# ESP8266_daughter_board.net
KiCad netlist of a schematic drawn in EAGLE
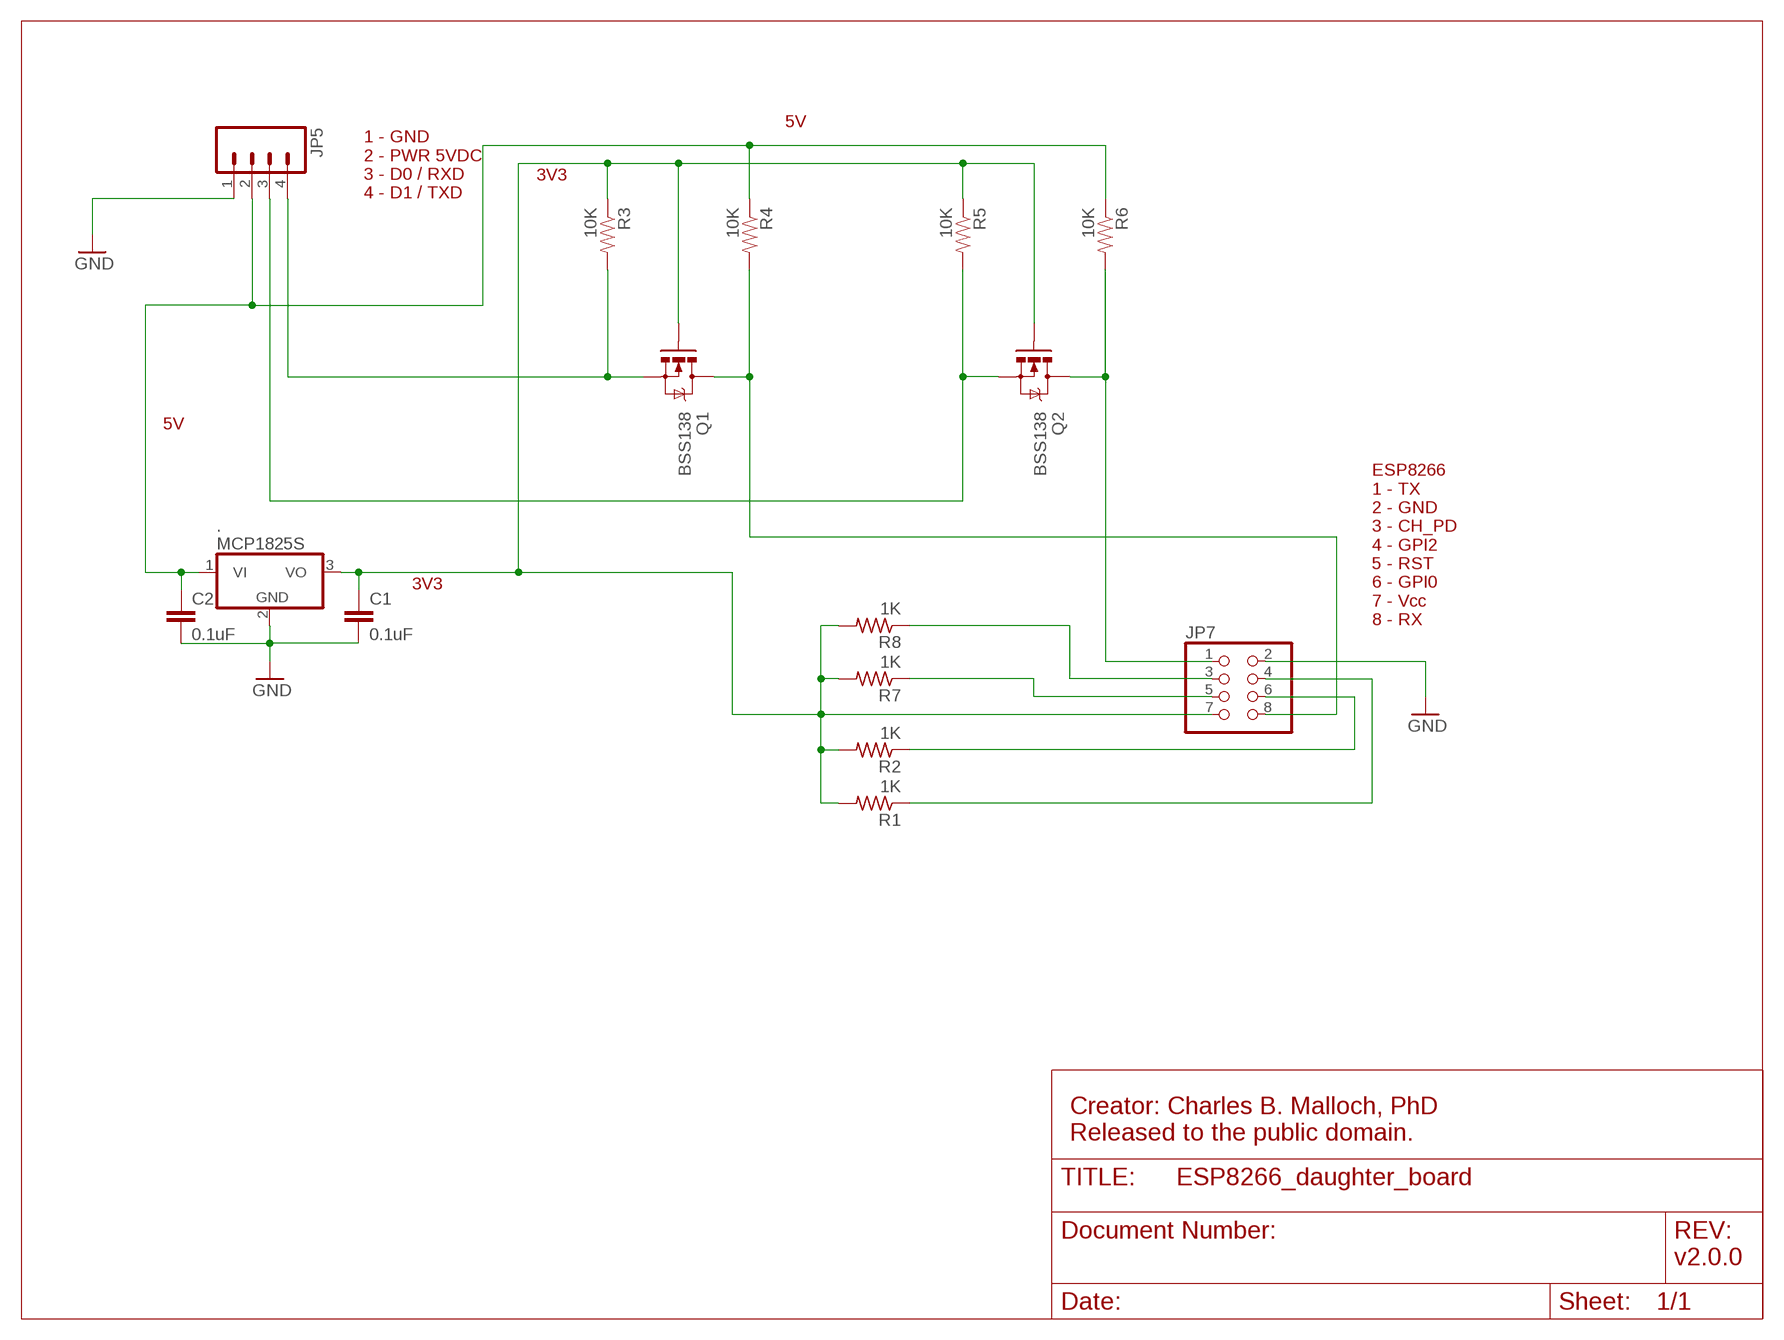
[diagram p0: schematic, sheet 1]

(export (version "E")
  (design (tool "Eeschema 10.0.6"))
  (components
    (comp (ref ".")
      (value "MCP1825S")
      (footprint "eagle-import:SOT223")
      (libsource (lib "eagle-import") (part "MCP1703DB"))
    )
    (comp (ref "C1")
      (value "0.1uF")
      (footprint "eagle-import:CAP-PTH-SMALLEZ")
      (libsource (lib "eagle-import") (part "CAPEZ"))
    )
    (comp (ref "C2")
      (value "0.1uF")
      (footprint "eagle-import:CAP-PTH-SMALLEZ")
      (libsource (lib "eagle-import") (part "CAPEZ"))
    )
    (comp (ref "JP5")
      (value "M04LOCK_LONGPADS")
      (footprint "eagle-import:1X04_LOCK_LONGPADS")
      (libsource (lib "eagle-import") (part "M04LOCK_LONGPADS"))
    )
    (comp (ref "JP7")
      (value "PINHD-2X4")
      (footprint "eagle-import:2X04")
      (libsource (lib "eagle-import") (part "PINHD-2X4"))
    )
    (comp (ref "Q1")
      (value "BSS138")
      (footprint "eagle-import:SOT23-3")
      (libsource (lib "eagle-import") (part "BSS138TRANS-00830"))
    )
    (comp (ref "Q2")
      (value "BSS138")
      (footprint "eagle-import:SOT23-3")
      (libsource (lib "eagle-import") (part "BSS138TRANS-00830"))
    )
    (comp (ref "R1")
      (value "1K")
      (footprint "eagle-import:0204_7")
      (libsource (lib "eagle-import") (part "R-US_0204/7"))
    )
    (comp (ref "R2")
      (value "1K")
      (footprint "eagle-import:0204_7")
      (libsource (lib "eagle-import") (part "R-US_0204/7"))
    )
    (comp (ref "R3")
      (value "10K")
      (footprint "eagle-import:1206")
      (libsource (lib "eagle-import") (part "RESISTOR1206"))
    )
    (comp (ref "R4")
      (value "10K")
      (footprint "eagle-import:1206")
      (libsource (lib "eagle-import") (part "RESISTOR1206"))
    )
    (comp (ref "R5")
      (value "10K")
      (footprint "eagle-import:1206")
      (libsource (lib "eagle-import") (part "RESISTOR1206"))
    )
    (comp (ref "R6")
      (value "10K")
      (footprint "eagle-import:1206")
      (libsource (lib "eagle-import") (part "RESISTOR1206"))
    )
    (comp (ref "R7")
      (value "1K")
      (footprint "eagle-import:0204_7")
      (libsource (lib "eagle-import") (part "R-US_0204/7"))
    )
    (comp (ref "R8")
      (value "1K")
      (footprint "eagle-import:0204_7")
      (libsource (lib "eagle-import") (part "R-US_0204/7"))
    )
  )
  (nets
    (net (code "1") (name "GND") (class "Default")
      (node (ref ".") (pin "2") (pinfunction "GND_2") (pintype "passive"))
      (node (ref "C1") (pin "2") (pinfunction "2_2") (pintype "passive"))
      (node (ref "C2") (pin "2") (pinfunction "2_2") (pintype "passive"))
      (node (ref "JP5") (pin "1") (pinfunction "1_1") (pintype "passive"))
      (node (ref "JP7") (pin "2") (pinfunction "2_2") (pintype "passive"))
    )
    (net (code "2") (name "Net-(.-VI)") (class "Default")
      (node (ref ".") (pin "1") (pinfunction "VI_1") (pintype "input"))
      (node (ref "C2") (pin "1") (pinfunction "1_1") (pintype "passive"))
      (node (ref "JP5") (pin "2") (pinfunction "2_2") (pintype "passive"))
      (node (ref "R4") (pin "1") (pinfunction "1_1") (pintype "passive"))
      (node (ref "R6") (pin "1") (pinfunction "1_1") (pintype "passive"))
    )
    (net (code "3") (name "Net-(.-VO)") (class "Default")
      (node (ref ".") (pin "3") (pinfunction "VO_3") (pintype "passive"))
      (node (ref "C1") (pin "1") (pinfunction "1_1") (pintype "passive"))
      (node (ref "JP7") (pin "7") (pinfunction "7_7") (pintype "passive"))
      (node (ref "Q1") (pin "1") (pinfunction "G_1") (pintype "passive"))
      (node (ref "Q2") (pin "1") (pinfunction "G_1") (pintype "passive"))
      (node (ref "R1") (pin "2") (pinfunction "2_2") (pintype "passive"))
      (node (ref "R2") (pin "2") (pinfunction "2_2") (pintype "passive"))
      (node (ref "R3") (pin "1") (pinfunction "1_1") (pintype "passive"))
      (node (ref "R5") (pin "1") (pinfunction "1_1") (pintype "passive"))
      (node (ref "R7") (pin "2") (pinfunction "2_2") (pintype "passive"))
      (node (ref "R8") (pin "2") (pinfunction "2_2") (pintype "passive"))
    )
    (net (code "4") (name "Net-(JP7-Pad3)") (class "Default")
      (node (ref "JP7") (pin "3") (pinfunction "3_3") (pintype "passive"))
      (node (ref "R8") (pin "1") (pinfunction "1_1") (pintype "passive"))
    )
    (net (code "5") (name "Net-(JP7-Pad4)") (class "Default")
      (node (ref "JP7") (pin "4") (pinfunction "4_4") (pintype "passive"))
      (node (ref "R1") (pin "1") (pinfunction "1_1") (pintype "passive"))
    )
    (net (code "6") (name "Net-(JP7-Pad5)") (class "Default")
      (node (ref "JP7") (pin "5") (pinfunction "5_5") (pintype "passive"))
      (node (ref "R7") (pin "1") (pinfunction "1_1") (pintype "passive"))
    )
    (net (code "7") (name "Net-(JP7-Pad6)") (class "Default")
      (node (ref "JP7") (pin "6") (pinfunction "6_6") (pintype "passive"))
      (node (ref "R2") (pin "1") (pinfunction "1_1") (pintype "passive"))
    )
    (net (code "8") (name "Net-(Q1-D)") (class "Default")
      (node (ref "JP7") (pin "8") (pinfunction "8_8") (pintype "passive"))
      (node (ref "Q1") (pin "3") (pinfunction "D_3") (pintype "passive"))
      (node (ref "R4") (pin "2") (pinfunction "2_2") (pintype "passive"))
    )
    (net (code "9") (name "Net-(Q1-S)") (class "Default")
      (node (ref "JP5") (pin "4") (pinfunction "4_4") (pintype "passive"))
      (node (ref "Q1") (pin "2") (pinfunction "S_2") (pintype "passive"))
      (node (ref "R3") (pin "2") (pinfunction "2_2") (pintype "passive"))
    )
    (net (code "10") (name "Net-(Q2-D)") (class "Default")
      (node (ref "JP7") (pin "1") (pinfunction "1_1") (pintype "passive"))
      (node (ref "Q2") (pin "3") (pinfunction "D_3") (pintype "passive"))
      (node (ref "R6") (pin "2") (pinfunction "2_2") (pintype "passive"))
    )
    (net (code "11") (name "Net-(Q2-S)") (class "Default")
      (node (ref "JP5") (pin "3") (pinfunction "3_3") (pintype "passive"))
      (node (ref "Q2") (pin "2") (pinfunction "S_2") (pintype "passive"))
      (node (ref "R5") (pin "2") (pinfunction "2_2") (pintype "passive"))
    )
  )
)
